# Schematic.net
KiCad netlist of a schematic drawn in EAGLE
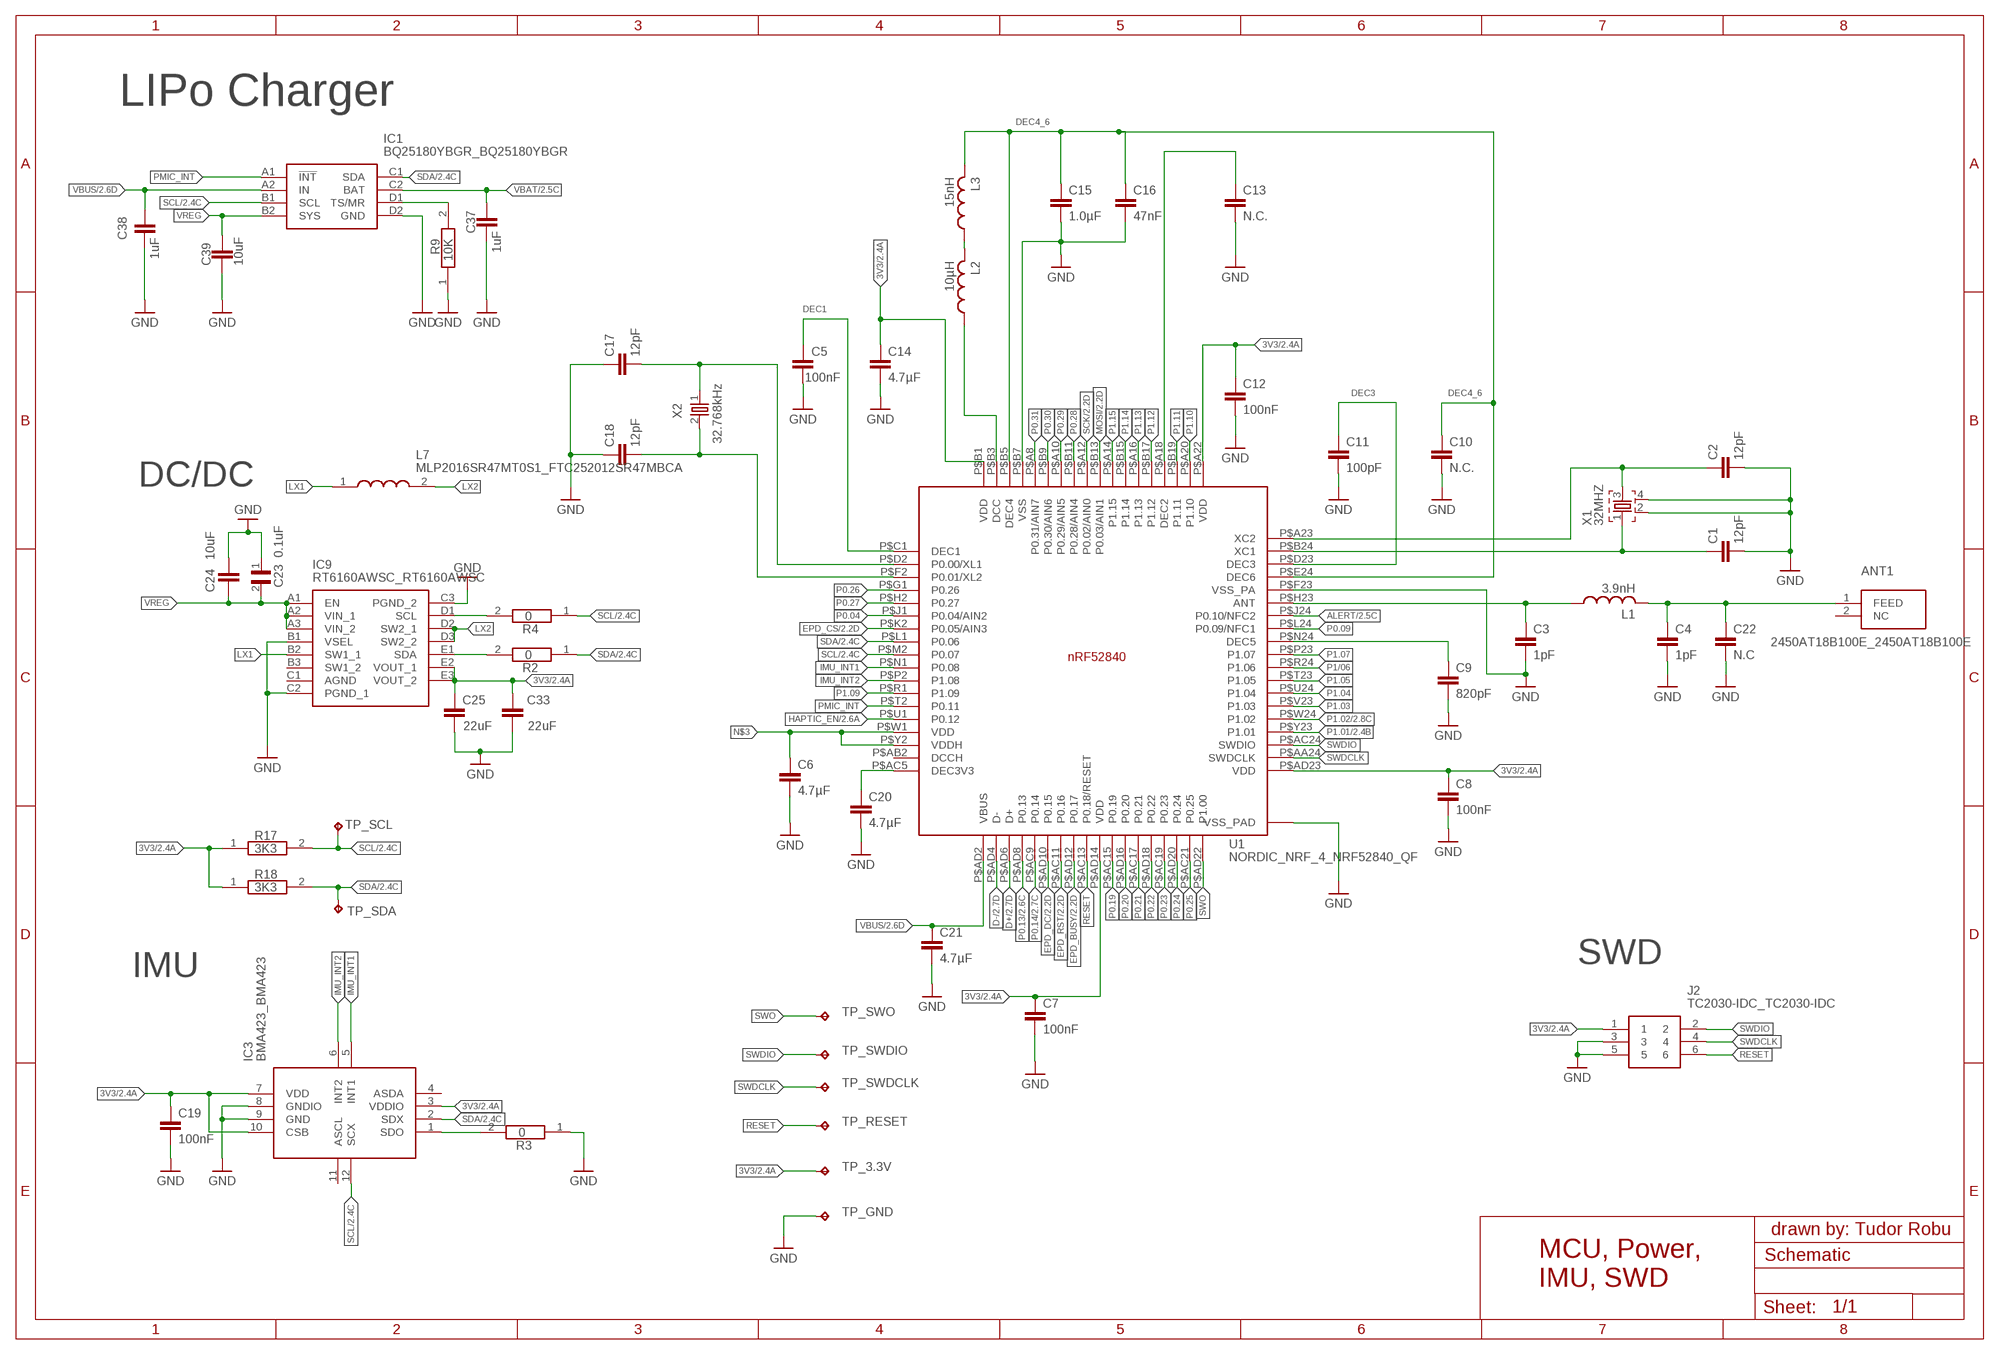
[diagram p0: schematic, sheet 1, part 1 of 2]
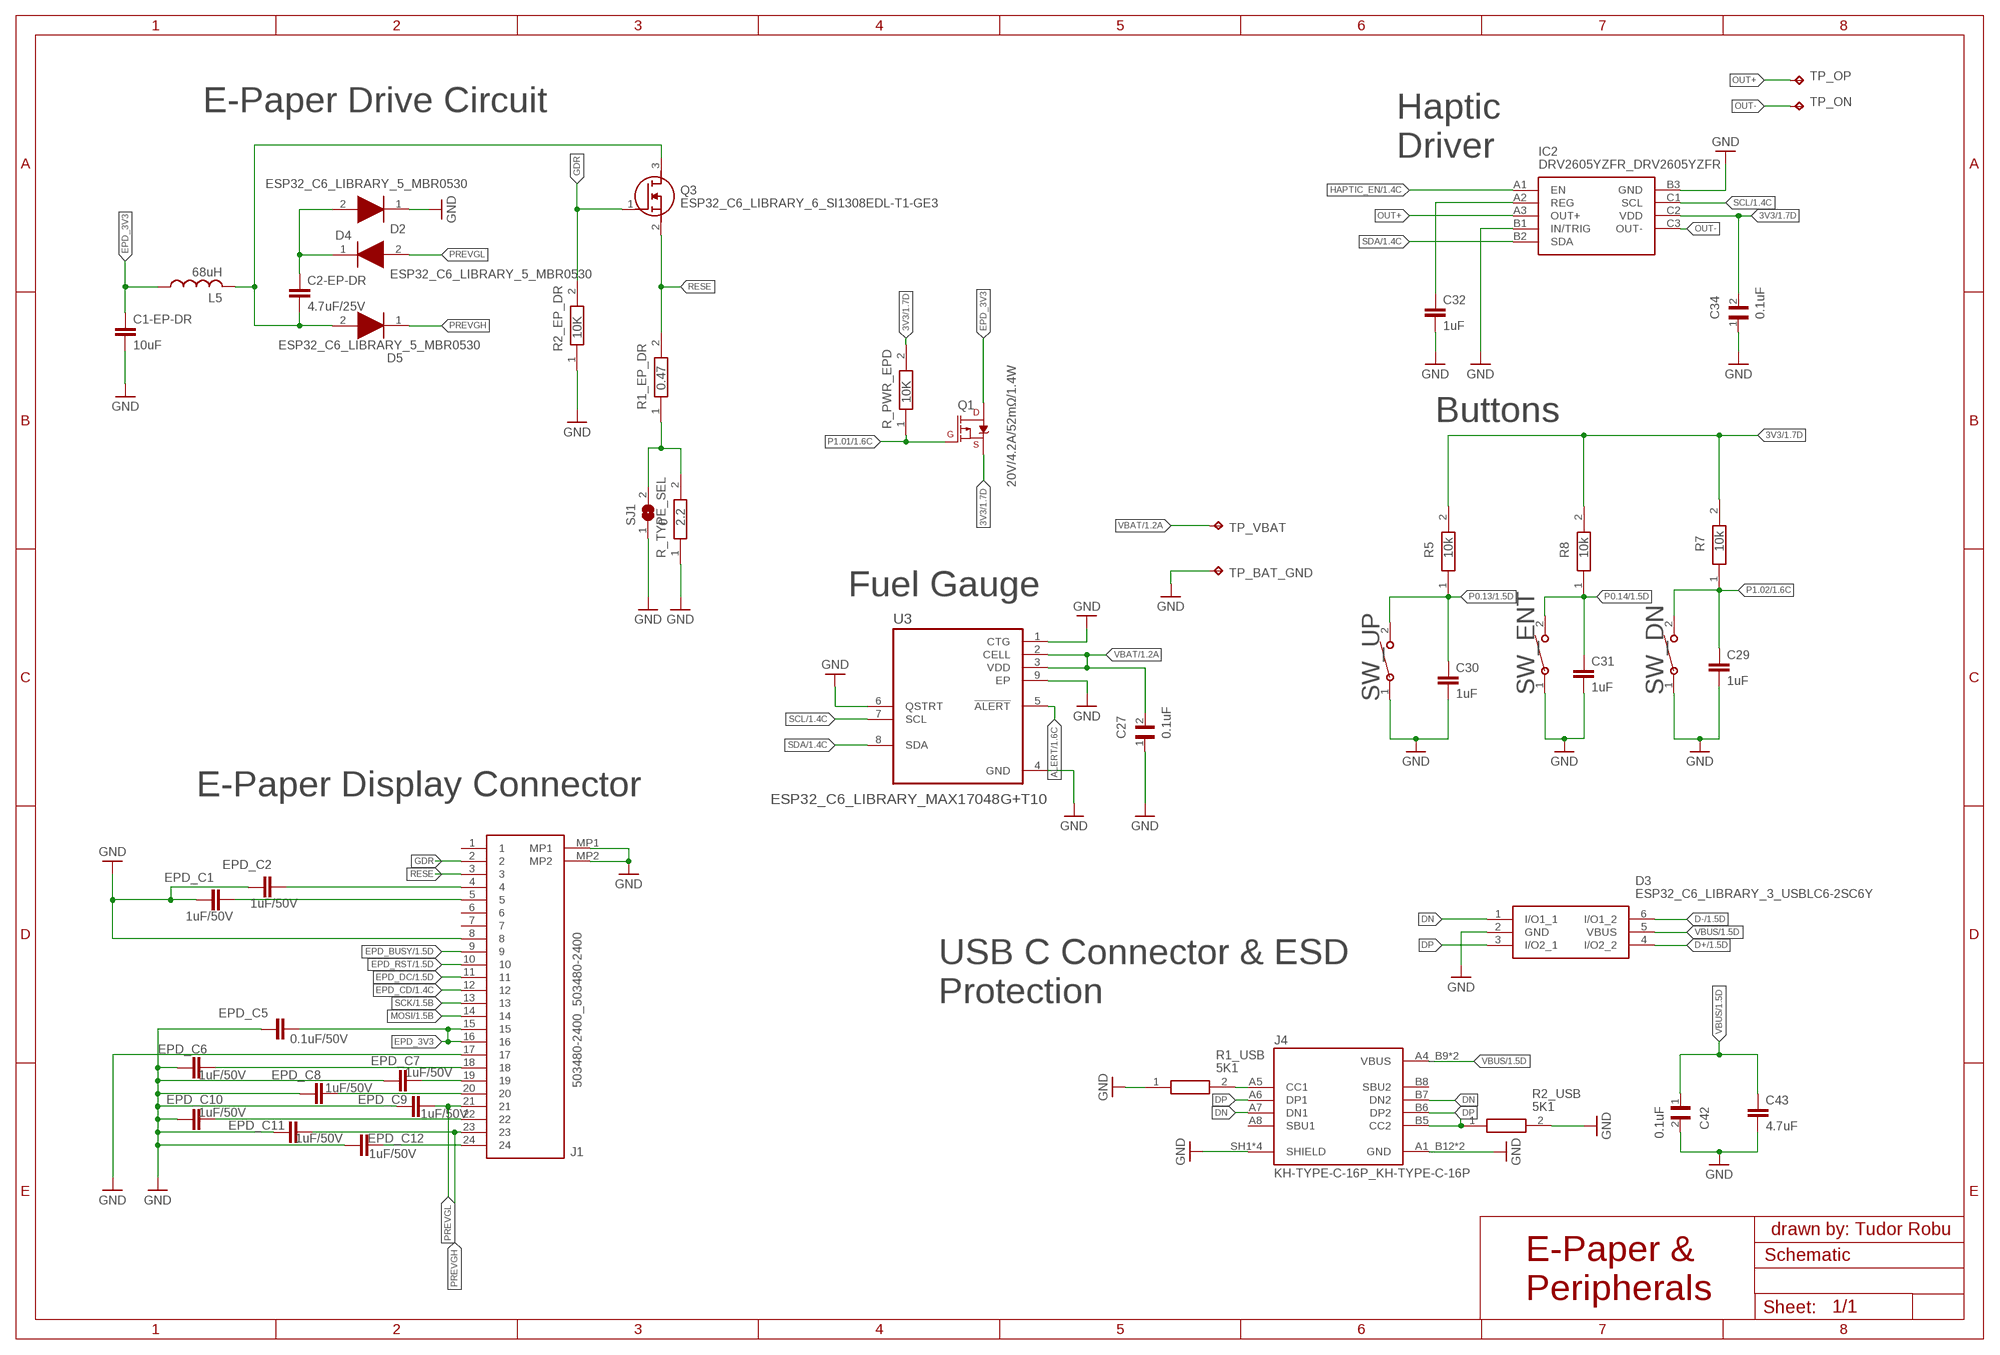
[diagram p1: schematic, sheet 1, part 2 of 2]

(export (version "E")
  (design (tool "Eeschema 10.0.6"))
  (components
    (comp (ref "ANT1")
      (value "2450AT18B100E_2450AT18B100E")
      (footprint "eagle-import:2450AT18B100E_ANTC3216X140N")
      (fields
        (field (name "ARROW_PART_NUMBER") "2450AT18B100E")
        (field (name "MOUSER_PART_NUMBER") "609-2450AT18B100E")
      )
      (libsource (lib "eagle-import") (part "2450AT18B100E_2450AT18B100E"))
    )
    (comp (ref "C1")
      (value "12pF")
      (footprint "eagle-import:NORDIC_NRF_3_RESC0201_L")
      (libsource (lib "eagle-import") (part "NORDIC_NRF_3_CAPACITOR_0201_L"))
    )
    (comp (ref "C1-EP-DR")
      (value "10uF")
      (footprint "eagle-import:PERFECT_0402_0402")
      (libsource (lib "eagle-import") (part "PERFECT_0402_CAP_0402"))
    )
    (comp (ref "C2")
      (value "12pF")
      (footprint "eagle-import:NORDIC_NRF_3_RESC0201_L")
      (libsource (lib "eagle-import") (part "NORDIC_NRF_3_CAPACITOR_0201_L"))
    )
    (comp (ref "C2-EP-DR")
      (value "4.7uF/25V")
      (footprint "eagle-import:PERFECT_0402_0402")
      (libsource (lib "eagle-import") (part "PERFECT_0402_CAP_0402"))
    )
    (comp (ref "C3")
      (value "1pF")
      (footprint "eagle-import:NORDIC_NRF_3_RESC0201_L")
      (libsource (lib "eagle-import") (part "NORDIC_NRF_3_CAPACITOR_0201_L"))
    )
    (comp (ref "C4")
      (value "1pF")
      (footprint "eagle-import:NORDIC_NRF_3_RESC0201_L")
      (libsource (lib "eagle-import") (part "NORDIC_NRF_3_CAPACITOR_0201_L"))
    )
    (comp (ref "C5")
      (value "100nF")
      (footprint "eagle-import:NORDIC_NRF_3_RESC0201_L")
      (libsource (lib "eagle-import") (part "NORDIC_NRF_3_CAPACITOR_0201_L"))
    )
    (comp (ref "C6")
      (value "4.7µF")
      (footprint "eagle-import:PERFECT_0402_0402")
      (libsource (lib "eagle-import") (part "PERFECT_0402_CAP_0402"))
    )
    (comp (ref "C7")
      (value "100nF")
      (footprint "eagle-import:PERFECT_0402_0402")
      (libsource (lib "eagle-import") (part "PERFECT_0402_CAP_0402"))
    )
    (comp (ref "C8")
      (value "100nF")
      (footprint "eagle-import:NORDIC_NRF_3_RESC0201_L")
      (libsource (lib "eagle-import") (part "NORDIC_NRF_3_CAPACITOR_0201_L"))
    )
    (comp (ref "C9")
      (value "820pF")
      (footprint "eagle-import:NORDIC_NRF_3_RESC0201_L")
      (libsource (lib "eagle-import") (part "NORDIC_NRF_3_CAPACITOR_0201_L"))
    )
    (comp (ref "C10")
      (value "N.C.")
      (footprint "eagle-import:NORDIC_NRF_3_RESC0201_L")
      (libsource (lib "eagle-import") (part "NORDIC_NRF_3_CAPACITOR_0201_L"))
    )
    (comp (ref "C11")
      (value "100pF")
      (footprint "eagle-import:NORDIC_NRF_3_RESC0201_L")
      (libsource (lib "eagle-import") (part "NORDIC_NRF_3_CAPACITOR_0201_L"))
    )
    (comp (ref "C12")
      (value "100nF")
      (footprint "eagle-import:NORDIC_NRF_3_RESC0201_L")
      (libsource (lib "eagle-import") (part "NORDIC_NRF_3_CAPACITOR_0201_L"))
    )
    (comp (ref "C13")
      (value "N.C.")
      (footprint "eagle-import:PERFECT_0402_0402")
      (libsource (lib "eagle-import") (part "PERFECT_0402_CAP_0402"))
    )
    (comp (ref "C14")
      (value "4.7µF")
      (footprint "eagle-import:PERFECT_0402_0402")
      (libsource (lib "eagle-import") (part "PERFECT_0402_CAP_0402"))
    )
    (comp (ref "C15")
      (value "1.0µF")
      (footprint "eagle-import:PERFECT_0402_0402")
      (libsource (lib "eagle-import") (part "PERFECT_0402_CAP_0402"))
    )
    (comp (ref "C16")
      (value "47nF")
      (footprint "eagle-import:NORDIC_NRF_3_RESC0201_L")
      (libsource (lib "eagle-import") (part "NORDIC_NRF_3_CAPACITOR_0201_L"))
    )
    (comp (ref "C17")
      (value "12pF")
      (footprint "eagle-import:NORDIC_NRF_3_RESC0201_L")
      (libsource (lib "eagle-import") (part "NORDIC_NRF_3_CAPACITOR_0201_L"))
    )
    (comp (ref "C18")
      (value "12pF")
      (footprint "eagle-import:NORDIC_NRF_3_RESC0201_L")
      (libsource (lib "eagle-import") (part "NORDIC_NRF_3_CAPACITOR_0201_L"))
    )
    (comp (ref "C19")
      (value "100nF")
      (footprint "eagle-import:NORDIC_NRF_3_RESC0201_L")
      (libsource (lib "eagle-import") (part "NORDIC_NRF_3_CAPACITOR_0201_L"))
    )
    (comp (ref "C20")
      (value "4.7µF")
      (footprint "eagle-import:PERFECT_0402_0402")
      (libsource (lib "eagle-import") (part "PERFECT_0402_CAP_0402"))
    )
    (comp (ref "C21")
      (value "4.7µF")
      (footprint "eagle-import:PERFECT_0402_0402")
      (libsource (lib "eagle-import") (part "PERFECT_0402_CAP_0402"))
    )
    (comp (ref "C22")
      (value "N.C")
      (footprint "eagle-import:NORDIC_NRF_3_RESC0201_L")
      (libsource (lib "eagle-import") (part "NORDIC_NRF_3_CAPACITOR_0201_L"))
    )
    (comp (ref "C23")
      (value "0.1uF")
      (footprint "eagle-import:GRM011R60J152KE01L_2_CAPC0201X13N")
      (fields (field (name "MF") "Murata") (field (name "MP") "GRM011R60J152KE01L"))
      (libsource (lib "eagle-import") (part "GRM011R60J152KE01L_2_GRM011R60J152KE01L"))
    )
    (comp (ref "C24")
      (value "10uF")
      (footprint "eagle-import:PERFECT_0402_0402")
      (libsource (lib "eagle-import") (part "PERFECT_0402_CAP_0402"))
    )
    (comp (ref "C25")
      (value "22uF")
      (footprint "eagle-import:PERFECT_0402_0402")
      (libsource (lib "eagle-import") (part "PERFECT_0402_CAP_0402"))
    )
    (comp (ref "C27")
      (value "0.1uF")
      (footprint "eagle-import:GRM011R60J152KE01L_2_CAPC0201X13N")
      (fields (field (name "MF") "Murata") (field (name "MP") "GRM011R60J152KE01L"))
      (libsource (lib "eagle-import") (part "GRM011R60J152KE01L_2_GRM011R60J152KE01L"))
    )
    (comp (ref "C29")
      (value "1uF")
      (footprint "eagle-import:PERFECT_0402_0402")
      (libsource (lib "eagle-import") (part "PERFECT_0402_CAP_0402"))
    )
    (comp (ref "C30")
      (value "1uF")
      (footprint "eagle-import:PERFECT_0402_0402")
      (libsource (lib "eagle-import") (part "PERFECT_0402_CAP_0402"))
    )
    (comp (ref "C31")
      (value "1uF")
      (footprint "eagle-import:PERFECT_0402_0402")
      (libsource (lib "eagle-import") (part "PERFECT_0402_CAP_0402"))
    )
    (comp (ref "C32")
      (value "1uF")
      (footprint "eagle-import:PERFECT_0402_0402")
      (libsource (lib "eagle-import") (part "PERFECT_0402_CAP_0402"))
    )
    (comp (ref "C33")
      (value "22uF")
      (footprint "eagle-import:PERFECT_0402_0402")
      (libsource (lib "eagle-import") (part "PERFECT_0402_CAP_0402"))
    )
    (comp (ref "C34")
      (value "0.1uF")
      (footprint "eagle-import:GRM011R60J152KE01L_2_CAPC0201X13N")
      (fields (field (name "MF") "Murata") (field (name "MP") "GRM011R60J152KE01L"))
      (libsource (lib "eagle-import") (part "GRM011R60J152KE01L_2_GRM011R60J152KE01L"))
    )
    (comp (ref "C37")
      (value "1uF")
      (footprint "eagle-import:PERFECT_0402_0402")
      (libsource (lib "eagle-import") (part "PERFECT_0402_CAP_0402"))
    )
    (comp (ref "C38")
      (value "1uF")
      (footprint "eagle-import:PERFECT_0402_0402")
      (libsource (lib "eagle-import") (part "PERFECT_0402_CAP_0402"))
    )
    (comp (ref "C39")
      (value "10uF")
      (footprint "eagle-import:PERFECT_0402_0402")
      (libsource (lib "eagle-import") (part "PERFECT_0402_CAP_0402"))
    )
    (comp (ref "C42")
      (value "0.1uF")
      (footprint "eagle-import:GRM011R60J152KE01L_2_CAPC0201X13N")
      (fields (field (name "MF") "Murata") (field (name "MP") "GRM011R60J152KE01L"))
      (libsource (lib "eagle-import") (part "GRM011R60J152KE01L_2_GRM011R60J152KE01L"))
    )
    (comp (ref "C43")
      (value "4.7uF")
      (footprint "eagle-import:PERFECT_0402_0402")
      (libsource (lib "eagle-import") (part "PERFECT_0402_CAP_0402"))
    )
    (comp (ref "D2")
      (value "ESP32_C6_LIBRARY_5_MBR0530")
      (footprint "eagle-import:ESP32_C6_LIBRARY_5_SOD3716X135N")
      (fields (field (name "MF") "ON Semiconductor") (field (name "MP") "MBR0530"))
      (libsource (lib "eagle-import") (part "ESP32_C6_LIBRARY_5_MBR0530"))
    )
    (comp (ref "D3")
      (value "ESP32_C6_LIBRARY_3_USBLC6-2SC6Y")
      (footprint "eagle-import:ESP32_C6_LIBRARY_3_SOT95P280X145-6N")
      (fields (field (name "MF") "STMicroelectronics") (field (name "MP") "USBLC6-2SC6Y"))
      (libsource (lib "eagle-import") (part "ESP32_C6_LIBRARY_3_USBLC6-2SC6Y"))
    )
    (comp (ref "D4")
      (value "ESP32_C6_LIBRARY_5_MBR0530")
      (footprint "eagle-import:ESP32_C6_LIBRARY_5_SOD3716X135N")
      (fields (field (name "MF") "ON Semiconductor") (field (name "MP") "MBR0530"))
      (libsource (lib "eagle-import") (part "ESP32_C6_LIBRARY_5_MBR0530"))
    )
    (comp (ref "D5")
      (value "ESP32_C6_LIBRARY_5_MBR0530")
      (footprint "eagle-import:ESP32_C6_LIBRARY_5_SOD3716X135N")
      (fields (field (name "MF") "ON Semiconductor") (field (name "MP") "MBR0530"))
      (libsource (lib "eagle-import") (part "ESP32_C6_LIBRARY_5_MBR0530"))
    )
    (comp (ref "EPD_C1")
      (value "1uF/50V")
      (footprint "eagle-import:PERFECT_0402_0402")
      (libsource (lib "eagle-import") (part "PERFECT_0402_CAP_0402"))
    )
    (comp (ref "EPD_C2")
      (value "1uF/50V")
      (footprint "eagle-import:PERFECT_0402_0402")
      (libsource (lib "eagle-import") (part "PERFECT_0402_CAP_0402"))
    )
    (comp (ref "EPD_C5")
      (value "0.1uF/50V")
      (footprint "eagle-import:NORDIC_NRF_3_RESC0201_L")
      (libsource (lib "eagle-import") (part "NORDIC_NRF_3_CAPACITOR_0201_L"))
    )
    (comp (ref "EPD_C6")
      (value "1uF/50V")
      (footprint "eagle-import:PERFECT_0402_0402")
      (libsource (lib "eagle-import") (part "PERFECT_0402_CAP_0402"))
    )
    (comp (ref "EPD_C7")
      (value "1uF/50V")
      (footprint "eagle-import:PERFECT_0402_0402")
      (libsource (lib "eagle-import") (part "PERFECT_0402_CAP_0402"))
    )
    (comp (ref "EPD_C8")
      (value "1uF/50V")
      (footprint "eagle-import:PERFECT_0402_0402")
      (libsource (lib "eagle-import") (part "PERFECT_0402_CAP_0402"))
    )
    (comp (ref "EPD_C9")
      (value "1uF/50V")
      (footprint "eagle-import:PERFECT_0402_0402")
      (libsource (lib "eagle-import") (part "PERFECT_0402_CAP_0402"))
    )
    (comp (ref "EPD_C10")
      (value "1uF/50V")
      (footprint "eagle-import:PERFECT_0402_0402")
      (libsource (lib "eagle-import") (part "PERFECT_0402_CAP_0402"))
    )
    (comp (ref "EPD_C11")
      (value "1uF/50V")
      (footprint "eagle-import:PERFECT_0402_0402")
      (libsource (lib "eagle-import") (part "PERFECT_0402_CAP_0402"))
    )
    (comp (ref "EPD_C12")
      (value "1uF/50V")
      (footprint "eagle-import:PERFECT_0402_0402")
      (libsource (lib "eagle-import") (part "PERFECT_0402_CAP_0402"))
    )
    (comp (ref "IC1")
      (value "BQ25180YBGR_BQ25180YBGR")
      (footprint "eagle-import:BQ25180YBGR_BGA8C40P2X4_100X155X50")
      (fields
        (field (name "ARROW_PART_NUMBER") "BQ25180YBGR")
        (field (name "MOUSER_PART_NUMBER") "595-BQ25180YBGR")
      )
      (libsource (lib "eagle-import") (part "BQ25180YBGR_BQ25180YBGR"))
    )
    (comp (ref "IC2")
      (value "DRV2605YZFR_DRV2605YZFR")
      (footprint "eagle-import:DRV2605YZFR_BGA9C50P3X3_144X144X62")
      (fields (field (name "ARROW_PART_NUMBER") "DRV2605YZFR"))
      (libsource (lib "eagle-import") (part "DRV2605YZFR_DRV2605YZFR"))
    )
    (comp (ref "IC3")
      (value "BMA423_BMA423")
      (footprint "eagle-import:BMA423_BMA423")
      (fields (field (name "ARROW_PART_NUMBER") "BMA423") (field (name "MOUSER_PART_NUMBER") "262-BMA423"))
      (libsource (lib "eagle-import") (part "BMA423_BMA423"))
    )
    (comp (ref "IC9")
      (value "RT6160AWSC_RT6160AWSC")
      (footprint "eagle-import:RT6160AWSC_BGA15C40P3X5_140X230X60")
      (fields
        (field (name "MANUFACTURER_PART_NUMBER") "RT6160AWSC")
        (field (name "MOUSER_PART_NUMBER") "835-RT6160AWSC")
      )
      (libsource (lib "eagle-import") (part "RT6160AWSC_RT6160AWSC"))
    )
    (comp (ref "J1")
      (value "503480-2400_503480-2400")
      (footprint "eagle-import:503480-2400_5034802400")
      (fields
        (field (name "MANUFACTURER_PART_NUMBER") "503480-2400")
        (field (name "MOUSER_PART_NUMBER") "538-503480-2400")
      )
      (libsource (lib "eagle-import") (part "503480-2400_503480-2400"))
    )
    (comp (ref "J2")
      (value "TC2030-IDC_TC2030-IDC")
      (footprint "eagle-import:TC2030-IDC_TC2030IDC")
      (fields (field (name "MANUFACTURER_PART_NUMBER") "TC2030-IDC"))
      (libsource (lib "eagle-import") (part "TC2030-IDC_TC2030-IDC"))
    )
    (comp (ref "J4")
      (value "KH-TYPE-C-16P_KH-TYPE-C-16P")
      (footprint "eagle-import:KH-TYPE-C-16P_KINGHELM_KH-TYPE-C-16P")
      (fields (field (name "MF") "kinghelm") (field (name "MP") "KH-TYPE-C-16P"))
      (libsource (lib "eagle-import") (part "KH-TYPE-C-16P_KH-TYPE-C-16P"))
    )
    (comp (ref "L1")
      (value "3.9nH")
      (footprint "eagle-import:NORDIC_NRF_2_RESC0402_L")
      (libsource (lib "eagle-import") (part "NORDIC_NRF_2_INDUCTOR_0402_L"))
    )
    (comp (ref "L2")
      (value "10µH")
      (footprint "eagle-import:NORDIC_NRF_2_RESC0402_L")
      (libsource (lib "eagle-import") (part "NORDIC_NRF_2_INDUCTOR_0402_L"))
    )
    (comp (ref "L3")
      (value "15nH")
      (footprint "eagle-import:NORDIC_NRF_2_RESC0402_L")
      (libsource (lib "eagle-import") (part "NORDIC_NRF_2_INDUCTOR_0402_L"))
    )
    (comp (ref "L5")
      (value "68uH")
      (footprint "eagle-import:NORDIC_NRF_2_RESC0402_L")
      (libsource (lib "eagle-import") (part "NORDIC_NRF_2_INDUCTOR_0402_L"))
    )
    (comp (ref "L7")
      (value "MLP2016SR47MT0S1_FTC252012SR47MBCA")
      (footprint "eagle-import:MLP2016SR47MT0S1_INDC2016X100N")
      (fields (field (name "MANUFACTURER_PART_NUMBER") "FTC252012SR47MBCA"))
      (libsource (lib "eagle-import") (part "MLP2016SR47MT0S1_FTC252012SR47MBCA"))
    )
    (comp (ref "Q1")
      (value "20V/4.2A/52mΩ/1.4W")
      (footprint "eagle-import:ESP32_C6_LIBRARY_4_ESP32_C6_LIBRARY_4_ESP32_C6_LIBRARY_4_ESP32_C6_LIBRARY_4_ESP32_WROVER_SPARKFUN-DISCRETESEMI_SOT23-3")
      (libsource (lib "eagle-import") (part "ESP32_C6_LIBRARY_4_ESP32_WROVER_SPARKFUN-DISCRETESEMI_MOSFET_PCH-DMG2305UX-7"))
    )
    (comp (ref "Q3")
      (value "ESP32_C6_LIBRARY_6_SI1308EDL-T1-GE3")
      (footprint "eagle-import:ESP32_C6_LIBRARY_6_SOT65P210X110-3N")
      (fields (field (name "MF") "Vishay Siliconix") (field (name "MP") "SI1308EDL-T1-GE3"))
      (libsource (lib "eagle-import") (part "ESP32_C6_LIBRARY_6_SI1308EDL-T1-GE3"))
    )
    (comp (ref "R1_EP_DR")
      (value "0.47")
      (footprint "eagle-import:CPF0201D7K68C1_0201")
      (libsource (lib "eagle-import") (part "CPF0201D7K68C1_CPF0201D7K68C1"))
    )
    (comp (ref "R1_USB")
      (value "5K1")
      (footprint "eagle-import:CPF0201D7K68C1_0201")
      (libsource (lib "eagle-import") (part "CPF0201D7K68C1_CPF0201D7K68C1"))
    )
    (comp (ref "R2")
      (value "0")
      (footprint "eagle-import:ERA-1AEB3401C_0201")
      (libsource (lib "eagle-import") (part "ERA-1AEB3401C_CPF0201D7K68C1"))
    )
    (comp (ref "R2_EP_DR")
      (value "10K")
      (footprint "eagle-import:CPF0201D7K68C1_0201")
      (libsource (lib "eagle-import") (part "CPF0201D7K68C1_CPF0201D7K68C1"))
    )
    (comp (ref "R2_USB")
      (value "5K1")
      (footprint "eagle-import:CPF0201D7K68C1_0201")
      (libsource (lib "eagle-import") (part "CPF0201D7K68C1_CPF0201D7K68C1"))
    )
    (comp (ref "R3")
      (value "0")
      (footprint "eagle-import:ERA-1AEB3401C_0201")
      (libsource (lib "eagle-import") (part "ERA-1AEB3401C_CPF0201D7K68C1"))
    )
    (comp (ref "R4")
      (value "0")
      (footprint "eagle-import:ERA-1AEB3401C_0201")
      (libsource (lib "eagle-import") (part "ERA-1AEB3401C_CPF0201D7K68C1"))
    )
    (comp (ref "R5")
      (value "10k")
      (footprint "eagle-import:CPF0201D7K68C1_0201")
      (libsource (lib "eagle-import") (part "CPF0201D7K68C1_CPF0201D7K68C1"))
    )
    (comp (ref "R7")
      (value "10k")
      (footprint "eagle-import:CPF0201D7K68C1_0201")
      (libsource (lib "eagle-import") (part "CPF0201D7K68C1_CPF0201D7K68C1"))
    )
    (comp (ref "R8")
      (value "10k")
      (footprint "eagle-import:CPF0201D7K68C1_0201")
      (libsource (lib "eagle-import") (part "CPF0201D7K68C1_CPF0201D7K68C1"))
    )
    (comp (ref "R9")
      (value "10K")
      (footprint "eagle-import:CPF0201D7K68C1_0201")
      (libsource (lib "eagle-import") (part "CPF0201D7K68C1_CPF0201D7K68C1"))
    )
    (comp (ref "R17")
      (value "3K3")
      (footprint "eagle-import:ERA-1AEB3401C_0201")
      (libsource (lib "eagle-import") (part "ERA-1AEB3401C_CPF0201D7K68C1"))
    )
    (comp (ref "R18")
      (value "3K3")
      (footprint "eagle-import:ERA-1AEB3401C_0201")
      (libsource (lib "eagle-import") (part "ERA-1AEB3401C_CPF0201D7K68C1"))
    )
    (comp (ref "R_PWR_EPD")
      (value "10K")
      (footprint "eagle-import:CPF0201D7K68C1_0201")
      (libsource (lib "eagle-import") (part "CPF0201D7K68C1_CPF0201D7K68C1"))
    )
    (comp (ref "R_TYPE_SEL")
      (value "2.2")
      (footprint "eagle-import:CPF0201D7K68C1_0201")
      (libsource (lib "eagle-import") (part "CPF0201D7K68C1_CPF0201D7K68C1"))
    )
    (comp (ref "SJ1")
      (value "0")
      (footprint "eagle-import:ESP32_C6_LIBRARY_7_JUMPER_SJ")
      (libsource (lib "eagle-import") (part "ESP32_C6_LIBRARY_7_JUMPER_SJ"))
    )
    (comp (ref "SW_DN")
      (value "2025-10-22_07-23-44_LIBRARY_EVP-AKE31ASW_EVP-AKE31A_PAN")
      (footprint "eagle-import:2025-10-22_07-23-44_LIBRARY_SW_EVP-AKE31A_PAN")
      (fields
        (field (name "MANUFACTURER_PART_NUMBER") "EVP-AKE31A")
        (field (name "COPYRIGHT") "Copyright (C) 2025 Ultra Librarian. All rights reserved.")
      )
      (libsource (lib "eagle-import") (part "2025-10-22_07-23-44_LIBRARY_EVP-AKE31ASW_EVP-AKE31A_PAN"))
    )
    (comp (ref "SW_ENT")
      (value "2025-10-22_07-23-44_LIBRARY_EVP-AKE31ASW_EVP-AKE31A_PAN")
      (footprint "eagle-import:2025-10-22_07-23-44_LIBRARY_SW_EVP-AKE31A_PAN")
      (fields
        (field (name "MANUFACTURER_PART_NUMBER") "EVP-AKE31A")
        (field (name "COPYRIGHT") "Copyright (C) 2025 Ultra Librarian. All rights reserved.")
      )
      (libsource (lib "eagle-import") (part "2025-10-22_07-23-44_LIBRARY_EVP-AKE31ASW_EVP-AKE31A_PAN"))
    )
    (comp (ref "SW_UP")
      (value "2025-10-22_07-23-44_LIBRARY_EVP-AKE31ASW_EVP-AKE31A_PAN")
      (footprint "eagle-import:2025-10-22_07-23-44_LIBRARY_SW_EVP-AKE31A_PAN")
      (fields
        (field (name "MANUFACTURER_PART_NUMBER") "EVP-AKE31A")
        (field (name "COPYRIGHT") "Copyright (C) 2025 Ultra Librarian. All rights reserved.")
      )
      (libsource (lib "eagle-import") (part "2025-10-22_07-23-44_LIBRARY_EVP-AKE31ASW_EVP-AKE31A_PAN"))
    )
    (comp (ref "TP_3.3V")
      (value "HECTOR_WATCH_1_TPTP20R")
      (footprint "eagle-import:HECTOR_WATCH_1_TP20R")
      (libsource (lib "eagle-import") (part "HECTOR_WATCH_1_TPTP20R"))
    )
    (comp (ref "TP_BAT_GND")
      (value "HECTOR_WATCH_1_TPTP20R")
      (footprint "eagle-import:HECTOR_WATCH_1_TP20R")
      (libsource (lib "eagle-import") (part "HECTOR_WATCH_1_TPTP20R"))
    )
    (comp (ref "TP_GND")
      (value "HECTOR_WATCH_1_TPTP20R")
      (footprint "eagle-import:HECTOR_WATCH_1_TP20R")
      (libsource (lib "eagle-import") (part "HECTOR_WATCH_1_TPTP20R"))
    )
    (comp (ref "TP_ON")
      (value "HECTOR_WATCH_1_TPTP20R")
      (footprint "eagle-import:HECTOR_WATCH_1_TP20R")
      (libsource (lib "eagle-import") (part "HECTOR_WATCH_1_TPTP20R"))
    )
    (comp (ref "TP_OP")
      (value "HECTOR_WATCH_1_TPTP20R")
      (footprint "eagle-import:HECTOR_WATCH_1_TP20R")
      (libsource (lib "eagle-import") (part "HECTOR_WATCH_1_TPTP20R"))
    )
    (comp (ref "TP_RESET")
      (value "HECTOR_WATCH_1_TPTP20R")
      (footprint "eagle-import:HECTOR_WATCH_1_TP20R")
      (libsource (lib "eagle-import") (part "HECTOR_WATCH_1_TPTP20R"))
    )
    (comp (ref "TP_SCL")
      (value "HECTOR_WATCH_1_TPTP20R")
      (footprint "eagle-import:HECTOR_WATCH_1_TP20R")
      (libsource (lib "eagle-import") (part "HECTOR_WATCH_1_TPTP20R"))
    )
    (comp (ref "TP_SDA")
      (value "HECTOR_WATCH_1_TPTP20R")
      (footprint "eagle-import:HECTOR_WATCH_1_TP20R")
      (libsource (lib "eagle-import") (part "HECTOR_WATCH_1_TPTP20R"))
    )
    (comp (ref "TP_SWDCLK")
      (value "HECTOR_WATCH_1_TPTP20R")
      (footprint "eagle-import:HECTOR_WATCH_1_TP20R")
      (libsource (lib "eagle-import") (part "HECTOR_WATCH_1_TPTP20R"))
    )
    (comp (ref "TP_SWDIO")
      (value "HECTOR_WATCH_1_TPTP20R")
      (footprint "eagle-import:HECTOR_WATCH_1_TP20R")
      (libsource (lib "eagle-import") (part "HECTOR_WATCH_1_TPTP20R"))
    )
    (comp (ref "TP_SWO")
      (value "HECTOR_WATCH_1_TPTP20R")
      (footprint "eagle-import:HECTOR_WATCH_1_TP20R")
      (libsource (lib "eagle-import") (part "HECTOR_WATCH_1_TPTP20R"))
    )
    (comp (ref "TP_VBAT")
      (value "HECTOR_WATCH_1_TPTP20R")
      (footprint "eagle-import:HECTOR_WATCH_1_TP20R")
      (libsource (lib "eagle-import") (part "HECTOR_WATCH_1_TPTP20R"))
    )
    (comp (ref "U1")
      (value "NORDIC_NRF_4_NRF52840_QF")
      (footprint "eagle-import:NORDIC_NRF_4_AQFN50P700X700X85_HS-74N")
      (libsource (lib "eagle-import") (part "NORDIC_NRF_4_NRF52840_QF"))
    )
    (comp (ref "U3")
      (value "ESP32_C6_LIBRARY_MAX17048G+T10")
      (footprint "eagle-import:ESP32_C6_LIBRARY_SON50P200X200X80-9N")
      (fields (field (name "MF") "Analog Devices") (field (name "MP") "MAX17048G+T10"))
      (libsource (lib "eagle-import") (part "ESP32_C6_LIBRARY_MAX17048G+T10"))
    )
    (comp (ref "X1")
      (value "32MHZ")
      (footprint "eagle-import:NORDIC_NRF_BT-XTAL_2016_N")
      (libsource (lib "eagle-import") (part "NORDIC_NRF_XTAL_32MHZ"))
    )
    (comp (ref "X2")
      (value "32.768kHz")
      (footprint "eagle-import:NORDIC_NRF_1_XTAL_3215_N")
      (libsource (lib "eagle-import") (part "NORDIC_NRF_1_XTAL_32KHZ"))
    )
  )
  (nets
    (net (code "1") (name "3V3{slash}1.7D") (class "Default")
      (node (ref "C34") (pin "2") (pinfunction "2_2") (pintype "passive"))
      (node (ref "IC2") (pin "C2") (pinfunction "VDD_C2") (pintype "bidirectional"))
      (node (ref "Q1") (pin "2") (pinfunction "S_2") (pintype "bidirectional"))
      (node (ref "R5") (pin "2") (pinfunction "2_2") (pintype "bidirectional"))
      (node (ref "R7") (pin "2") (pinfunction "2_2") (pintype "bidirectional"))
      (node (ref "R8") (pin "2") (pinfunction "2_2") (pintype "bidirectional"))
      (node (ref "R_PWR_EPD") (pin "2") (pinfunction "2_2") (pintype "bidirectional"))
    )
    (net (code "2") (name "3V3{slash}2.4A") (class "Default")
      (node (ref "C12") (pin "1") (pinfunction "1_1") (pintype "passive"))
      (node (ref "C14") (pin "1") (pinfunction "1_1") (pintype "passive"))
      (node (ref "C19") (pin "1") (pinfunction "1_1") (pintype "passive"))
      (node (ref "C25") (pin "2") (pinfunction "2_2") (pintype "passive"))
      (node (ref "C33") (pin "2") (pinfunction "2_2") (pintype "passive"))
      (node (ref "C7") (pin "1") (pinfunction "1_1") (pintype "passive"))
      (node (ref "C8") (pin "1") (pinfunction "1_1") (pintype "passive"))
      (node (ref "IC3") (pin "10") (pinfunction "CSB_10") (pintype "bidirectional"))
      (node (ref "IC3") (pin "3") (pinfunction "VDDIO_3") (pintype "bidirectional"))
      (node (ref "IC3") (pin "7") (pinfunction "VDD_7") (pintype "bidirectional"))
      (node (ref "IC9") (pin "E2") (pinfunction "VOUT_1_E2") (pintype "bidirectional"))
      (node (ref "IC9") (pin "E3") (pinfunction "VOUT_2_E3") (pintype "bidirectional"))
      (node (ref "J2") (pin "1") (pinfunction "1_1") (pintype "bidirectional"))
      (node (ref "R17") (pin "1") (pinfunction "1_1") (pintype "bidirectional"))
      (node (ref "R18") (pin "1") (pinfunction "1_1") (pintype "bidirectional"))
      (node (ref "TP_3.3V") (pin "TP") (pinfunction "TP_TP") (pintype "input"))
      (node (ref "U1") (pin "P$A22") (pinfunction "VDD_P$A22") (pintype "power_in"))
      (node (ref "U1") (pin "P$AD14") (pinfunction "VDD_P$AD14") (pintype "power_in"))
      (node (ref "U1") (pin "P$AD23") (pinfunction "VDD_P$AD23") (pintype "power_in"))
      (node (ref "U1") (pin "P$B1") (pinfunction "VDD_P$B1") (pintype "power_in"))
    )
    (net (code "3") (name "ALERT{slash}1.6C") (class "Default")
      (node (ref "U3") (pin "5") (pinfunction "~{ALERT}_5") (pintype "output"))
    )
    (net (code "4") (name "ALERT{slash}2.5C") (class "Default")
      (node (ref "U1") (pin "P$J24") (pinfunction "P0.10/NFC2_P$J24") (pintype "bidirectional"))
    )
    (net (code "5") (name "D+{slash}1.5D") (class "Default")
      (node (ref "D3") (pin "4") (pinfunction "I/O2_2_4") (pintype "bidirectional"))
    )
    (net (code "6") (name "D+{slash}2.7D") (class "Default")
      (node (ref "U1") (pin "P$AD6") (pinfunction "D+_P$AD6") (pintype "bidirectional"))
    )
    (net (code "7") (name "D-{slash}1.5D") (class "Default")
      (node (ref "D3") (pin "6") (pinfunction "I/O1_2_6") (pintype "bidirectional"))
    )
    (net (code "8") (name "D-{slash}2.7D") (class "Default")
      (node (ref "U1") (pin "P$AD4") (pinfunction "D-_P$AD4") (pintype "bidirectional"))
    )
    (net (code "9") (name "DN") (class "Default")
      (node (ref "D3") (pin "1") (pinfunction "I/O1_1_1") (pintype "bidirectional"))
      (node (ref "J4") (pin "A7") (pinfunction "DN1_A7") (pintype "bidirectional"))
      (node (ref "J4") (pin "B7") (pinfunction "DN2_B7") (pintype "bidirectional"))
    )
    (net (code "10") (name "DP") (class "Default")
      (node (ref "D3") (pin "3") (pinfunction "I/O2_1_3") (pintype "bidirectional"))
      (node (ref "J4") (pin "A6") (pinfunction "DP1_A6") (pintype "bidirectional"))
      (node (ref "J4") (pin "B6") (pinfunction "DP2_B6") (pintype "bidirectional"))
    )
    (net (code "11") (name "EPD_3V3") (class "Default")
      (node (ref "C1-EP-DR") (pin "1") (pinfunction "1_1") (pintype "passive"))
      (node (ref "EPD_C5") (pin "2") (pinfunction "2_2") (pintype "passive"))
      (node (ref "J1") (pin "15") (pinfunction "15_15") (pintype "bidirectional"))
      (node (ref "J1") (pin "16") (pinfunction "16_16") (pintype "bidirectional"))
      (node (ref "L5") (pin "1") (pinfunction "1_1") (pintype "passive"))
      (node (ref "Q1") (pin "3") (pinfunction "D_3") (pintype "bidirectional"))
    )
    (net (code "12") (name "EPD_BUSY{slash}1.5D") (class "Default")
      (node (ref "J1") (pin "9") (pinfunction "9_9") (pintype "bidirectional"))
    )
    (net (code "13") (name "EPD_BUSY{slash}2.2D") (class "Default")
      (node (ref "U1") (pin "P$AC11") (pinfunction "P0.16_P$AC11") (pintype "bidirectional"))
    )
    (net (code "14") (name "EPD_CD{slash}1.4C") (class "Default")
      (node (ref "J1") (pin "12") (pinfunction "12_12") (pintype "bidirectional"))
    )
    (net (code "15") (name "EPD_CS{slash}2.2D") (class "Default")
      (node (ref "U1") (pin "P$K2") (pinfunction "P0.05/AIN3_P$K2") (pintype "bidirectional"))
    )
    (net (code "16") (name "EPD_DC{slash}1.5D") (class "Default")
      (node (ref "J1") (pin "11") (pinfunction "11_11") (pintype "bidirectional"))
    )
    (net (code "17") (name "EPD_DC{slash}2.2D") (class "Default")
      (node (ref "U1") (pin "P$AD10") (pinfunction "P0.15_P$AD10") (pintype "bidirectional"))
    )
    (net (code "18") (name "EPD_RST{slash}1.5D") (class "Default")
      (node (ref "J1") (pin "10") (pinfunction "10_10") (pintype "bidirectional"))
    )
    (net (code "19") (name "EPD_RST{slash}2.2D") (class "Default")
      (node (ref "U1") (pin "P$AD12") (pinfunction "P0.17_P$AD12") (pintype "bidirectional"))
    )
    (net (code "20") (name "GDR") (class "Default")
      (node (ref "J1") (pin "2") (pinfunction "2_2") (pintype "bidirectional"))
      (node (ref "Q3") (pin "1") (pinfunction "G_1") (pintype "bidirectional"))
      (node (ref "R2_EP_DR") (pin "2") (pinfunction "2_2") (pintype "bidirectional"))
    )
    (net (code "21") (name "GND") (class "Default")
      (node (ref "C1") (pin "2") (pinfunction "2_2") (pintype "passive"))
      (node (ref "C1-EP-DR") (pin "2") (pinfunction "2_2") (pintype "passive"))
      (node (ref "C10") (pin "2") (pinfunction "2_2") (pintype "passive"))
      (node (ref "C11") (pin "2") (pinfunction "2_2") (pintype "passive"))
      (node (ref "C12") (pin "2") (pinfunction "2_2") (pintype "passive"))
      (node (ref "C13") (pin "2") (pinfunction "2_2") (pintype "passive"))
      (node (ref "C14") (pin "2") (pinfunction "2_2") (pintype "passive"))
      (node (ref "C15") (pin "2") (pinfunction "2_2") (pintype "passive"))
      (node (ref "C16") (pin "2") (pinfunction "2_2") (pintype "passive"))
      (node (ref "C17") (pin "1") (pinfunction "1_1") (pintype "passive"))
      (node (ref "C18") (pin "1") (pinfunction "1_1") (pintype "passive"))
      (node (ref "C19") (pin "2") (pinfunction "2_2") (pintype "passive"))
      (node (ref "C2") (pin "2") (pinfunction "2_2") (pintype "passive"))
      (node (ref "C20") (pin "2") (pinfunction "2_2") (pintype "passive"))
      (node (ref "C21") (pin "2") (pinfunction "2_2") (pintype "passive"))
      (node (ref "C22") (pin "2") (pinfunction "2_2") (pintype "passive"))
      (node (ref "C23") (pin "1") (pinfunction "1_1") (pintype "passive"))
      (node (ref "C24") (pin "2") (pinfunction "2_2") (pintype "passive"))
      (node (ref "C25") (pin "1") (pinfunction "1_1") (pintype "passive"))
      (node (ref "C27") (pin "1") (pinfunction "1_1") (pintype "passive"))
      (node (ref "C29") (pin "2") (pinfunction "2_2") (pintype "passive"))
      (node (ref "C3") (pin "2") (pinfunction "2_2") (pintype "passive"))
      (node (ref "C30") (pin "2") (pinfunction "2_2") (pintype "passive"))
      (node (ref "C31") (pin "2") (pinfunction "2_2") (pintype "passive"))
      (node (ref "C32") (pin "2") (pinfunction "2_2") (pintype "passive"))
      (node (ref "C33") (pin "1") (pinfunction "1_1") (pintype "passive"))
      (node (ref "C34") (pin "1") (pinfunction "1_1") (pintype "passive"))
      (node (ref "C37") (pin "2") (pinfunction "2_2") (pintype "passive"))
      (node (ref "C38") (pin "2") (pinfunction "2_2") (pintype "passive"))
      (node (ref "C39") (pin "2") (pinfunction "2_2") (pintype "passive"))
      (node (ref "C4") (pin "2") (pinfunction "2_2") (pintype "passive"))
      (node (ref "C42") (pin "2") (pinfunction "2_2") (pintype "passive"))
      (node (ref "C43") (pin "2") (pinfunction "2_2") (pintype "passive"))
      (node (ref "C5") (pin "1") (pinfunction "1_1") (pintype "passive"))
      (node (ref "C6") (pin "2") (pinfunction "2_2") (pintype "passive"))
      (node (ref "C7") (pin "2") (pinfunction "2_2") (pintype "passive"))
      (node (ref "C8") (pin "2") (pinfunction "2_2") (pintype "passive"))
      (node (ref "C9") (pin "2") (pinfunction "2_2") (pintype "passive"))
      (node (ref "D3") (pin "2") (pinfunction "GND_2") (pintype "bidirectional"))
      (node (ref "D4") (pin "1") (pinfunction "K_1") (pintype "bidirectional"))
      (node (ref "EPD_C1") (pin "1") (pinfunction "1_1") (pintype "passive"))
      (node (ref "EPD_C10") (pin "1") (pinfunction "1_1") (pintype "passive"))
      (node (ref "EPD_C11") (pin "1") (pinfunction "1_1") (pintype "passive"))
      (node (ref "EPD_C12") (pin "1") (pinfunction "1_1") (pintype "passive"))
      (node (ref "EPD_C2") (pin "1") (pinfunction "1_1") (pintype "passive"))
      (node (ref "EPD_C5") (pin "1") (pinfunction "1_1") (pintype "passive"))
      (node (ref "EPD_C6") (pin "1") (pinfunction "1_1") (pintype "passive"))
      (node (ref "EPD_C7") (pin "1") (pinfunction "1_1") (pintype "passive"))
      (node (ref "EPD_C8") (pin "1") (pinfunction "1_1") (pintype "passive"))
      (node (ref "EPD_C9") (pin "1") (pinfunction "1_1") (pintype "passive"))
      (node (ref "IC1") (pin "D2") (pinfunction "GND_D2") (pintype "bidirectional"))
      (node (ref "IC2") (pin "B1") (pinfunction "IN/TRIG_B1") (pintype "bidirectional"))
      (node (ref "IC2") (pin "B3") (pinfunction "GND_B3") (pintype "bidirectional"))
      (node (ref "IC3") (pin "8") (pinfunction "GNDIO_8") (pintype "bidirectional"))
      (node (ref "IC3") (pin "9") (pinfunction "GND_9") (pintype "bidirectional"))
      (node (ref "IC9") (pin "B1") (pinfunction "VSEL_B1") (pintype "bidirectional"))
      (node (ref "IC9") (pin "C2") (pinfunction "PGND_1_C2") (pintype "bidirectional"))
      (node (ref "IC9") (pin "C3") (pinfunction "PGND_2_C3") (pintype "bidirectional"))
      (node (ref "J1") (pin "17") (pinfunction "17_17") (pintype "bidirectional"))
      (node (ref "J1") (pin "8") (pinfunction "8_8") (pintype "bidirectional"))
      (node (ref "J1") (pin "MP1") (pinfunction "MP1_MP1") (pintype "bidirectional"))
      (node (ref "J1") (pin "MP2") (pinfunction "MP2_MP2") (pintype "bidirectional"))
      (node (ref "J2") (pin "3") (pinfunction "3_3") (pintype "bidirectional"))
      (node (ref "J2") (pin "5") (pinfunction "5_5") (pintype "bidirectional"))
      (node (ref "J4") (pin "A12_B1") (pinfunction "GND_A12_B1") (pintype "power_in"))
      (node (ref "J4") (pin "A1_B12") (pinfunction "GND_A1_B12") (pintype "power_in"))
      (node (ref "J4") (pin "SH1") (pinfunction "SHIELD_SH1") (pintype "passive"))
      (node (ref "J4") (pin "SH2") (pinfunction "SHIELD_SH2") (pintype "passive"))
      (node (ref "J4") (pin "SH3") (pinfunction "SHIELD_SH3") (pintype "passive"))
      (node (ref "J4") (pin "SH4") (pinfunction "SHIELD_SH4") (pintype "passive"))
      (node (ref "R1_USB") (pin "1") (pinfunction "1_1") (pintype "bidirectional"))
      (node (ref "R2_EP_DR") (pin "1") (pinfunction "1_1") (pintype "bidirectional"))
      (node (ref "R2_USB") (pin "2") (pinfunction "2_2") (pintype "bidirectional"))
      (node (ref "R3") (pin "1") (pinfunction "1_1") (pintype "bidirectional"))
      (node (ref "R9") (pin "1") (pinfunction "1_1") (pintype "bidirectional"))
      (node (ref "R_TYPE_SEL") (pin "1") (pinfunction "1_1") (pintype "bidirectional"))
      (node (ref "SJ1") (pin "1") (pinfunction "1_1") (pintype "passive"))
      (node (ref "SW_DN") (pin "1") (pinfunction "1_1") (pintype "passive"))
      (node (ref "SW_ENT") (pin "1") (pinfunction "1_1") (pintype "passive"))
      (node (ref "SW_UP") (pin "1") (pinfunction "1_1") (pintype "passive"))
      (node (ref "TP_BAT_GND") (pin "TP") (pinfunction "TP_TP") (pintype "input"))
      (node (ref "TP_GND") (pin "TP") (pinfunction "TP_TP") (pintype "input"))
      (node (ref "U1") (pin "P$74") (pinfunction "VSS_PAD_P$74") (pintype "bidirectional"))
      (node (ref "U1") (pin "P$75") (pinfunction "VSS_PAD_P$75") (pintype "bidirectional"))
      (node (ref "U1") (pin "P$76") (pinfunction "VSS_PAD_P$76") (pintype "bidirectional"))
      (node (ref "U1") (pin "P$77") (pinfunction "VSS_PAD_P$77") (pintype "bidirectional"))
      (node (ref "U1") (pin "P$78") (pinfunction "VSS_PAD_P$78") (pintype "bidirectional"))
      (node (ref "U1") (pin "P$79") (pinfunction "VSS_PAD_P$79") (pintype "bidirectional"))
      (node (ref "U1") (pin "P$80") (pinfunction "VSS_PAD_P$80") (pintype "bidirectional"))
      (node (ref "U1") (pin "P$81") (pinfunction "VSS_PAD_P$81") (pintype "bidirectional"))
      (node (ref "U1") (pin "P$82") (pinfunction "VSS_PAD_P$82") (pintype "bidirectional"))
      (node (ref "U1") (pin "P$83") (pinfunction "VSS_PAD_P$83") (pintype "bidirectional"))
      (node (ref "U1") (pin "P$84") (pinfunction "VSS_PAD_P$84") (pintype "bidirectional"))
      (node (ref "U1") (pin "P$85") (pinfunction "VSS_PAD_P$85") (pintype "bidirectional"))
      (node (ref "U1") (pin "P$86") (pinfunction "VSS_PAD_P$86") (pintype "bidirectional"))
      (node (ref "U1") (pin "P$87") (pinfunction "VSS_PAD_P$87") (pintype "bidirectional"))
      (node (ref "U1") (pin "P$88") (pinfunction "VSS_PAD_P$88") (pintype "bidirectional"))
      (node (ref "U1") (pin "P$89") (pinfunction "VSS_PAD_P$89") (pintype "bidirectional"))
      (node (ref "U1") (pin "P$90") (pinfunction "VSS_PAD_P$90") (pintype "bidirectional"))
      (node (ref "U1") (pin "P$B7") (pinfunction "VSS_P$B7") (pintype "power_in"))
      (node (ref "U1") (pin "P$F23") (pinfunction "VSS_PA_P$F23") (pintype "bidirectional"))
      (node (ref "U3") (pin "1") (pinfunction "CTG_1") (pintype "power_in"))
      (node (ref "U3") (pin "4") (pinfunction "GND_4") (pintype "power_in"))
      (node (ref "U3") (pin "6") (pinfunction "QSTRT_6") (pintype "input"))
      (node (ref "U3") (pin "9") (pinfunction "EP_9") (pintype "power_in"))
      (node (ref "X1") (pin "2") (pinfunction "2_2") (pintype "passive"))
      (node (ref "X1") (pin "4") (pinfunction "4_4") (pintype "passive"))
    )
    (net (code "22") (name "HAPTIC_EN{slash}1.4C") (class "Default")
      (node (ref "IC2") (pin "A1") (pinfunction "EN_A1") (pintype "bidirectional"))
    )
    (net (code "23") (name "HAPTIC_EN{slash}2.6A") (class "Default")
      (node (ref "U1") (pin "P$U1") (pinfunction "P0.12_P$U1") (pintype "bidirectional"))
    )
    (net (code "24") (name "IMU_INT1") (class "Default")
      (node (ref "IC3") (pin "5") (pinfunction "INT1_5") (pintype "bidirectional"))
      (node (ref "U1") (pin "P$N1") (pinfunction "P0.08_P$N1") (pintype "bidirectional"))
    )
    (net (code "25") (name "IMU_INT2") (class "Default")
      (node (ref "IC3") (pin "6") (pinfunction "INT2_6") (pintype "bidirectional"))
      (node (ref "U1") (pin "P$P2") (pinfunction "P1.08_P$P2") (pintype "bidirectional"))
    )
    (net (code "26") (name "LX1") (class "Default")
      (node (ref "IC9") (pin "B2") (pinfunction "SW1_1_B2") (pintype "bidirectional"))
      (node (ref "L7") (pin "1") (pinfunction "1_1") (pintype "bidirectional"))
    )
    (net (code "27") (name "LX2") (class "Default")
      (node (ref "IC9") (pin "D2") (pinfunction "SW2_1_D2") (pintype "bidirectional"))
      (node (ref "IC9") (pin "D3") (pinfunction "SW2_2_D3") (pintype "bidirectional"))
      (node (ref "L7") (pin "2") (pinfunction "2_2") (pintype "bidirectional"))
    )
    (net (code "28") (name "MOSI{slash}1.5B") (class "Default")
      (node (ref "J1") (pin "14") (pinfunction "14_14") (pintype "bidirectional"))
    )
    (net (code "29") (name "MOSI{slash}2.2D") (class "Default")
      (node (ref "U1") (pin "P$B13") (pinfunction "P0.03/AIN1_P$B13") (pintype "bidirectional"))
    )
    (net (code "30") (name "N$3") (class "Default")
      (node (ref "C6") (pin "1") (pinfunction "1_1") (pintype "passive"))
      (node (ref "U1") (pin "P$W1") (pinfunction "VDD_P$W1") (pintype "power_in"))
      (node (ref "U1") (pin "P$Y2") (pinfunction "VDDH_P$Y2") (pintype "power_in"))
    )
    (net (code "31") (name "Net-(ANT1-FEED)") (class "Default")
      (node (ref "ANT1") (pin "1") (pinfunction "FEED_1") (pintype "input"))
      (node (ref "C22") (pin "1") (pinfunction "1_1") (pintype "passive"))
      (node (ref "C4") (pin "1") (pinfunction "1_1") (pintype "passive"))
      (node (ref "L1") (pin "2") (pinfunction "2_2") (pintype "passive"))
    )
    (net (code "32") (name "Net-(D2-K)") (class "Default")
      (node (ref "C2-EP-DR") (pin "1") (pinfunction "1_1") (pintype "passive"))
      (node (ref "D2") (pin "1") (pinfunction "K_1") (pintype "bidirectional"))
      (node (ref "D4") (pin "2") (pinfunction "A_2") (pintype "bidirectional"))
    )
    (net (code "33") (name "Net-(D5-A)") (class "Default")
      (node (ref "C2-EP-DR") (pin "2") (pinfunction "2_2") (pintype "passive"))
      (node (ref "D5") (pin "2") (pinfunction "A_2") (pintype "bidirectional"))
      (node (ref "L5") (pin "2") (pinfunction "2_2") (pintype "passive"))
      (node (ref "Q3") (pin "3") (pinfunction "D_3") (pintype "bidirectional"))
    )
    (net (code "34") (name "Net-(EPD_C1-Pad2)") (class "Default")
      (node (ref "EPD_C1") (pin "2") (pinfunction "2_2") (pintype "passive"))
      (node (ref "J1") (pin "5") (pinfunction "5_5") (pintype "bidirectional"))
    )
    (net (code "35") (name "Net-(EPD_C2-Pad2)") (class "Default")
      (node (ref "EPD_C2") (pin "2") (pinfunction "2_2") (pintype "passive"))
      (node (ref "J1") (pin "4") (pinfunction "4_4") (pintype "bidirectional"))
    )
    (net (code "36") (name "Net-(EPD_C6-Pad2)") (class "Default")
      (node (ref "EPD_C6") (pin "2") (pinfunction "2_2") (pintype "passive"))
      (node (ref "J1") (pin "18") (pinfunction "18_18") (pintype "bidirectional"))
    )
    (net (code "37") (name "Net-(EPD_C7-Pad2)") (class "Default")
      (node (ref "EPD_C7") (pin "2") (pinfunction "2_2") (pintype "passive"))
      (node (ref "J1") (pin "19") (pinfunction "19_19") (pintype "bidirectional"))
    )
    (net (code "38") (name "Net-(EPD_C8-Pad2)") (class "Default")
      (node (ref "EPD_C8") (pin "2") (pinfunction "2_2") (pintype "passive"))
      (node (ref "J1") (pin "20") (pinfunction "20_20") (pintype "bidirectional"))
    )
    (net (code "39") (name "Net-(EPD_C10-Pad2)") (class "Default")
      (node (ref "EPD_C10") (pin "2") (pinfunction "2_2") (pintype "passive"))
      (node (ref "J1") (pin "22") (pinfunction "22_22") (pintype "bidirectional"))
    )
    (net (code "40") (name "Net-(EPD_C12-Pad2)") (class "Default")
      (node (ref "EPD_C12") (pin "2") (pinfunction "2_2") (pintype "passive"))
      (node (ref "J1") (pin "24") (pinfunction "24_24") (pintype "bidirectional"))
    )
    (net (code "41") (name "Net-(IC1-TS{slash}MR)") (class "Default")
      (node (ref "IC1") (pin "D1") (pinfunction "TS/MR_D1") (pintype "bidirectional"))
      (node (ref "R9") (pin "2") (pinfunction "2_2") (pintype "bidirectional"))
    )
    (net (code "42") (name "Net-(IC2-REG)") (class "Default")
      (node (ref "C32") (pin "1") (pinfunction "1_1") (pintype "passive"))
      (node (ref "IC2") (pin "A2") (pinfunction "REG_A2") (pintype "bidirectional"))
    )
    (net (code "43") (name "Net-(IC3-SDO)") (class "Default")
      (node (ref "IC3") (pin "1") (pinfunction "SDO_1") (pintype "bidirectional"))
      (node (ref "R3") (pin "2") (pinfunction "2_2") (pintype "bidirectional"))
    )
    (net (code "44") (name "Net-(IC9-SCL)") (class "Default")
      (node (ref "IC9") (pin "D1") (pinfunction "SCL_D1") (pintype "bidirectional"))
      (node (ref "R4") (pin "2") (pinfunction "2_2") (pintype "bidirectional"))
    )
    (net (code "45") (name "Net-(IC9-SDA)") (class "Default")
      (node (ref "IC9") (pin "E1") (pinfunction "SDA_E1") (pintype "bidirectional"))
      (node (ref "R2") (pin "2") (pinfunction "2_2") (pintype "bidirectional"))
    )
    (net (code "46") (name "Net-(J4-CC1)") (class "Default")
      (node (ref "J4") (pin "A5") (pinfunction "CC1_A5") (pintype "bidirectional"))
      (node (ref "R1_USB") (pin "2") (pinfunction "2_2") (pintype "bidirectional"))
    )
    (net (code "47") (name "Net-(J4-CC2)") (class "Default")
      (node (ref "J4") (pin "B5") (pinfunction "CC2_B5") (pintype "bidirectional"))
      (node (ref "R2_USB") (pin "1") (pinfunction "1_1") (pintype "bidirectional"))
    )
    (net (code "48") (name "Net-(L2-Pad2)") (class "Default")
      (node (ref "L2") (pin "2") (pinfunction "2_2") (pintype "passive"))
      (node (ref "L3") (pin "1") (pinfunction "1_1") (pintype "passive"))
    )
    (net (code "49") (name "Net-(R1_EP_DR-Pad1)") (class "Default")
      (node (ref "R1_EP_DR") (pin "1") (pinfunction "1_1") (pintype "bidirectional"))
      (node (ref "R_TYPE_SEL") (pin "2") (pinfunction "2_2") (pintype "bidirectional"))
      (node (ref "SJ1") (pin "2") (pinfunction "2_2") (pintype "passive"))
    )
    (net (code "50") (name "Net-(U1-ANT)") (class "Default")
      (node (ref "C3") (pin "1") (pinfunction "1_1") (pintype "passive"))
      (node (ref "L1") (pin "1") (pinfunction "1_1") (pintype "passive"))
      (node (ref "U1") (pin "P$H23") (pinfunction "ANT_P$H23") (pintype "bidirectional"))
    )
    (net (code "51") (name "Net-(U1-DCC)") (class "Default")
      (node (ref "L2") (pin "1") (pinfunction "1_1") (pintype "passive"))
      (node (ref "U1") (pin "P$B3") (pinfunction "DCC_P$B3") (pintype "output"))
    )
    (net (code "52") (name "Net-(U1-DEC1)") (class "Default")
      (node (ref "C5") (pin "2") (pinfunction "2_2") (pintype "passive"))
      (node (ref "U1") (pin "P$C1") (pinfunction "DEC1_P$C1") (pintype "power_in"))
    )
    (net (code "53") (name "Net-(U1-DEC2)") (class "Default")
      (node (ref "C13") (pin "1") (pinfunction "1_1") (pintype "passive"))
      (node (ref "U1") (pin "P$A18") (pinfunction "DEC2_P$A18") (pintype "bidirectional"))
    )
    (net (code "54") (name "Net-(U1-DEC3)") (class "Default")
      (node (ref "C11") (pin "1") (pinfunction "1_1") (pintype "passive"))
      (node (ref "U1") (pin "P$D23") (pinfunction "DEC3_P$D23") (pintype "bidirectional"))
    )
    (net (code "55") (name "Net-(U1-DEC3V3)") (class "Default")
      (node (ref "C20") (pin "1") (pinfunction "1_1") (pintype "passive"))
      (node (ref "U1") (pin "P$AC5") (pinfunction "DEC3V3_P$AC5") (pintype "bidirectional"))
    )
    (net (code "56") (name "Net-(U1-DEC4)") (class "Default")
      (node (ref "C10") (pin "1") (pinfunction "1_1") (pintype "passive"))
      (node (ref "C15") (pin "1") (pinfunction "1_1") (pintype "passive"))
      (node (ref "C16") (pin "1") (pinfunction "1_1") (pintype "passive"))
      (node (ref "L3") (pin "2") (pinfunction "2_2") (pintype "passive"))
      (node (ref "U1") (pin "P$B5") (pinfunction "DEC4_P$B5") (pintype "power_in"))
      (node (ref "U1") (pin "P$E24") (pinfunction "DEC6_P$E24") (pintype "bidirectional"))
    )
    (net (code "57") (name "Net-(U1-DEC5)") (class "Default")
      (node (ref "C9") (pin "1") (pinfunction "1_1") (pintype "passive"))
      (node (ref "U1") (pin "P$N24") (pinfunction "DEC5_P$N24") (pintype "bidirectional"))
    )
    (net (code "58") (name "Net-(U1-P0.00{slash}XL1)") (class "Default")
      (node (ref "C17") (pin "2") (pinfunction "2_2") (pintype "passive"))
      (node (ref "U1") (pin "P$D2") (pinfunction "P0.00/XL1_P$D2") (pintype "bidirectional"))
      (node (ref "X2") (pin "1") (pinfunction "1_1") (pintype "passive"))
    )
    (net (code "59") (name "Net-(U1-P0.01{slash}XL2)") (class "Default")
      (node (ref "C18") (pin "2") (pinfunction "2_2") (pintype "passive"))
      (node (ref "U1") (pin "P$F2") (pinfunction "P0.01/XL2_P$F2") (pintype "bidirectional"))
      (node (ref "X2") (pin "2") (pinfunction "2_2") (pintype "passive"))
    )
    (net (code "60") (name "Net-(U1-XC1)") (class "Default")
      (node (ref "C1") (pin "1") (pinfunction "1_1") (pintype "passive"))
      (node (ref "U1") (pin "P$B24") (pinfunction "XC1_P$B24") (pintype "input"))
      (node (ref "X1") (pin "1") (pinfunction "1_1") (pintype "passive"))
    )
    (net (code "61") (name "Net-(U1-XC2)") (class "Default")
      (node (ref "C2") (pin "1") (pinfunction "1_1") (pintype "passive"))
      (node (ref "U1") (pin "P$A23") (pinfunction "XC2_P$A23") (pintype "output"))
      (node (ref "X1") (pin "3") (pinfunction "3_3") (pintype "passive"))
    )
    (net (code "62") (name "OUT+") (class "Default")
      (node (ref "IC2") (pin "A3") (pinfunction "OUT+_A3") (pintype "bidirectional"))
      (node (ref "TP_OP") (pin "TP") (pinfunction "TP_TP") (pintype "input"))
    )
    (net (code "63") (name "OUT-") (class "Default")
      (node (ref "IC2") (pin "C3") (pinfunction "OUT-_C3") (pintype "bidirectional"))
      (node (ref "TP_ON") (pin "TP") (pinfunction "TP_TP") (pintype "input"))
    )
    (net (code "64") (name "P0.04") (class "Default")
      (node (ref "U1") (pin "P$J1") (pinfunction "P0.04/AIN2_P$J1") (pintype "bidirectional"))
    )
    (net (code "65") (name "P0.09") (class "Default")
      (node (ref "U1") (pin "P$L24") (pinfunction "P0.09/NFC1_P$L24") (pintype "bidirectional"))
    )
    (net (code "66") (name "P0.13{slash}1.5D") (class "Default")
      (node (ref "C30") (pin "1") (pinfunction "1_1") (pintype "passive"))
      (node (ref "R5") (pin "1") (pinfunction "1_1") (pintype "bidirectional"))
      (node (ref "SW_UP") (pin "2") (pinfunction "2_2") (pintype "passive"))
    )
    (net (code "67") (name "P0.13{slash}2.6C") (class "Default")
      (node (ref "U1") (pin "P$AD8") (pinfunction "P0.13_P$AD8") (pintype "bidirectional"))
    )
    (net (code "68") (name "P0.14{slash}1.5D") (class "Default")
      (node (ref "C31") (pin "1") (pinfunction "1_1") (pintype "passive"))
      (node (ref "R8") (pin "1") (pinfunction "1_1") (pintype "bidirectional"))
      (node (ref "SW_ENT") (pin "2") (pinfunction "2_2") (pintype "passive"))
    )
    (net (code "69") (name "P0.14{slash}2.7C") (class "Default")
      (node (ref "U1") (pin "P$AC9") (pinfunction "P0.14_P$AC9") (pintype "bidirectional"))
    )
    (net (code "70") (name "P0.19") (class "Default")
      (node (ref "U1") (pin "P$AC15") (pinfunction "P0.19_P$AC15") (pintype "bidirectional"))
    )
    (net (code "71") (name "P0.20") (class "Default")
      (node (ref "U1") (pin "P$AD16") (pinfunction "P0.20_P$AD16") (pintype "bidirectional"))
    )
    (net (code "72") (name "P0.21") (class "Default")
      (node (ref "U1") (pin "P$AC17") (pinfunction "P0.21_P$AC17") (pintype "bidirectional"))
    )
    (net (code "73") (name "P0.22") (class "Default")
      (node (ref "U1") (pin "P$AD18") (pinfunction "P0.22_P$AD18") (pintype "bidirectional"))
    )
    (net (code "74") (name "P0.23") (class "Default")
      (node (ref "U1") (pin "P$AC19") (pinfunction "P0.23_P$AC19") (pintype "bidirectional"))
    )
    (net (code "75") (name "P0.24") (class "Default")
      (node (ref "U1") (pin "P$AD20") (pinfunction "P0.24_P$AD20") (pintype "bidirectional"))
    )
    (net (code "76") (name "P0.25") (class "Default")
      (node (ref "U1") (pin "P$AC21") (pinfunction "P0.25_P$AC21") (pintype "bidirectional"))
    )
    (net (code "77") (name "P0.26") (class "Default")
      (node (ref "U1") (pin "P$G1") (pinfunction "P0.26_P$G1") (pintype "bidirectional"))
    )
    (net (code "78") (name "P0.27") (class "Default")
      (node (ref "U1") (pin "P$H2") (pinfunction "P0.27_P$H2") (pintype "bidirectional"))
    )
    (net (code "79") (name "P0.28") (class "Default")
      (node (ref "U1") (pin "P$B11") (pinfunction "P0.28/AIN4_P$B11") (pintype "bidirectional"))
    )
    (net (code "80") (name "P0.29") (class "Default")
      (node (ref "U1") (pin "P$A10") (pinfunction "P0.29/AIN5_P$A10") (pintype "bidirectional"))
    )
    (net (code "81") (name "P0.30") (class "Default")
      (node (ref "U1") (pin "P$B9") (pinfunction "P0.30/AIN6_P$B9") (pintype "bidirectional"))
    )
    (net (code "82") (name "P0.31") (class "Default")
      (node (ref "U1") (pin "P$A8") (pinfunction "P0.31/AIN7_P$A8") (pintype "bidirectional"))
    )
    (net (code "83") (name "P1.01{slash}1.6C") (class "Default")
      (node (ref "Q1") (pin "1") (pinfunction "G_1") (pintype "bidirectional"))
      (node (ref "R_PWR_EPD") (pin "1") (pinfunction "1_1") (pintype "bidirectional"))
    )
    (net (code "84") (name "P1.01{slash}2.4B") (class "Default")
      (node (ref "U1") (pin "P$Y23") (pinfunction "P1.01_P$Y23") (pintype "bidirectional"))
    )
    (net (code "85") (name "P1.02{slash}1.6C") (class "Default")
      (node (ref "C29") (pin "1") (pinfunction "1_1") (pintype "passive"))
      (node (ref "R7") (pin "1") (pinfunction "1_1") (pintype "bidirectional"))
      (node (ref "SW_DN") (pin "2") (pinfunction "2_2") (pintype "passive"))
    )
    (net (code "86") (name "P1.02{slash}2.8C") (class "Default")
      (node (ref "U1") (pin "P$W24") (pinfunction "P1.02_P$W24") (pintype "bidirectional"))
    )
    (net (code "87") (name "P1.03") (class "Default")
      (node (ref "U1") (pin "P$V23") (pinfunction "P1.03_P$V23") (pintype "bidirectional"))
    )
    (net (code "88") (name "P1.04") (class "Default")
      (node (ref "U1") (pin "P$U24") (pinfunction "P1.04_P$U24") (pintype "bidirectional"))
    )
    (net (code "89") (name "P1.05") (class "Default")
      (node (ref "U1") (pin "P$T23") (pinfunction "P1.05_P$T23") (pintype "bidirectional"))
    )
    (net (code "90") (name "P1.07") (class "Default")
      (node (ref "U1") (pin "P$P23") (pinfunction "P1.07_P$P23") (pintype "bidirectional"))
    )
    (net (code "91") (name "P1.09") (class "Default")
      (node (ref "U1") (pin "P$R1") (pinfunction "P1.09_P$R1") (pintype "bidirectional"))
    )
    (net (code "92") (name "P1.10") (class "Default")
      (node (ref "U1") (pin "P$A20") (pinfunction "P1.10_P$A20") (pintype "bidirectional"))
    )
    (net (code "93") (name "P1.11") (class "Default")
      (node (ref "U1") (pin "P$B19") (pinfunction "P1.11_P$B19") (pintype "bidirectional"))
    )
    (net (code "94") (name "P1.12") (class "Default")
      (node (ref "U1") (pin "P$B17") (pinfunction "P1.12_P$B17") (pintype "bidirectional"))
    )
    (net (code "95") (name "P1.13") (class "Default")
      (node (ref "U1") (pin "P$A16") (pinfunction "P1.13_P$A16") (pintype "bidirectional"))
    )
    (net (code "96") (name "P1.14") (class "Default")
      (node (ref "U1") (pin "P$B15") (pinfunction "P1.14_P$B15") (pintype "bidirectional"))
    )
    (net (code "97") (name "P1.15") (class "Default")
      (node (ref "U1") (pin "P$A14") (pinfunction "P1.15_P$A14") (pintype "bidirectional"))
    )
    (net (code "98") (name "P1{slash}06") (class "Default")
      (node (ref "U1") (pin "P$R24") (pinfunction "P1.06_P$R24") (pintype "bidirectional"))
    )
    (net (code "99") (name "PMIC_INT") (class "Default")
      (node (ref "IC1") (pin "A1") (pinfunction "~{INT}_A1") (pintype "bidirectional"))
      (node (ref "U1") (pin "P$T2") (pinfunction "P0.11_P$T2") (pintype "bidirectional"))
    )
    (net (code "100") (name "PREVGH") (class "Default")
      (node (ref "D5") (pin "1") (pinfunction "K_1") (pintype "bidirectional"))
      (node (ref "EPD_C11") (pin "2") (pinfunction "2_2") (pintype "passive"))
      (node (ref "J1") (pin "23") (pinfunction "23_23") (pintype "bidirectional"))
    )
    (net (code "101") (name "PREVGL") (class "Default")
      (node (ref "D2") (pin "2") (pinfunction "A_2") (pintype "bidirectional"))
      (node (ref "EPD_C9") (pin "2") (pinfunction "2_2") (pintype "passive"))
      (node (ref "J1") (pin "21") (pinfunction "21_21") (pintype "bidirectional"))
    )
    (net (code "102") (name "RESE") (class "Default")
      (node (ref "J1") (pin "3") (pinfunction "3_3") (pintype "bidirectional"))
      (node (ref "Q3") (pin "2") (pinfunction "S_2") (pintype "bidirectional"))
      (node (ref "R1_EP_DR") (pin "2") (pinfunction "2_2") (pintype "bidirectional"))
    )
    (net (code "103") (name "RESET") (class "Default")
      (node (ref "J2") (pin "6") (pinfunction "6_6") (pintype "bidirectional"))
      (node (ref "TP_RESET") (pin "TP") (pinfunction "TP_TP") (pintype "input"))
      (node (ref "U1") (pin "P$AC13") (pinfunction "P0.18/RESET_P$AC13") (pintype "bidirectional"))
    )
    (net (code "104") (name "SCK{slash}1.5B") (class "Default")
      (node (ref "J1") (pin "13") (pinfunction "13_13") (pintype "bidirectional"))
    )
    (net (code "105") (name "SCK{slash}2.2D") (class "Default")
      (node (ref "U1") (pin "P$A12") (pinfunction "P0.02/AIN0_P$A12") (pintype "bidirectional"))
    )
    (net (code "106") (name "SCL{slash}1.4C") (class "Default")
      (node (ref "IC2") (pin "C1") (pinfunction "SCL_C1") (pintype "bidirectional"))
      (node (ref "U3") (pin "7") (pinfunction "SCL_7") (pintype "input"))
    )
    (net (code "107") (name "SCL{slash}2.4C") (class "Default")
      (node (ref "IC1") (pin "B1") (pinfunction "SCL_B1") (pintype "bidirectional"))
      (node (ref "IC3") (pin "12") (pinfunction "SCX_12") (pintype "bidirectional"))
      (node (ref "R17") (pin "2") (pinfunction "2_2") (pintype "bidirectional"))
      (node (ref "R4") (pin "1") (pinfunction "1_1") (pintype "bidirectional"))
      (node (ref "TP_SCL") (pin "TP") (pinfunction "TP_TP") (pintype "input"))
      (node (ref "U1") (pin "P$M2") (pinfunction "P0.07_P$M2") (pintype "bidirectional"))
    )
    (net (code "108") (name "SDA{slash}1.4C") (class "Default")
      (node (ref "IC2") (pin "B2") (pinfunction "SDA_B2") (pintype "bidirectional"))
      (node (ref "U3") (pin "8") (pinfunction "SDA_8") (pintype "bidirectional"))
    )
    (net (code "109") (name "SDA{slash}2.4C") (class "Default")
      (node (ref "IC1") (pin "C1") (pinfunction "SDA_C1") (pintype "bidirectional"))
      (node (ref "IC3") (pin "2") (pinfunction "SDX_2") (pintype "bidirectional"))
      (node (ref "R18") (pin "2") (pinfunction "2_2") (pintype "bidirectional"))
      (node (ref "R2") (pin "1") (pinfunction "1_1") (pintype "bidirectional"))
      (node (ref "TP_SDA") (pin "TP") (pinfunction "TP_TP") (pintype "input"))
      (node (ref "U1") (pin "P$L1") (pinfunction "P0.06_P$L1") (pintype "bidirectional"))
    )
    (net (code "110") (name "SWDCLK") (class "Default")
      (node (ref "J2") (pin "4") (pinfunction "4_4") (pintype "bidirectional"))
      (node (ref "TP_SWDCLK") (pin "TP") (pinfunction "TP_TP") (pintype "input"))
      (node (ref "U1") (pin "P$AA24") (pinfunction "SWDCLK_P$AA24") (pintype "input"))
    )
    (net (code "111") (name "SWDIO") (class "Default")
      (node (ref "J2") (pin "2") (pinfunction "2_2") (pintype "bidirectional"))
      (node (ref "TP_SWDIO") (pin "TP") (pinfunction "TP_TP") (pintype "input"))
      (node (ref "U1") (pin "P$AC24") (pinfunction "SWDIO_P$AC24") (pintype "bidirectional"))
    )
    (net (code "112") (name "SWO") (class "Default")
      (node (ref "TP_SWO") (pin "TP") (pinfunction "TP_TP") (pintype "input"))
      (node (ref "U1") (pin "P$AD22") (pinfunction "P1.00_P$AD22") (pintype "bidirectional"))
    )
    (net (code "113") (name "VBAT{slash}1.2A") (class "Default")
      (node (ref "C27") (pin "2") (pinfunction "2_2") (pintype "passive"))
      (node (ref "TP_VBAT") (pin "TP") (pinfunction "TP_TP") (pintype "input"))
      (node (ref "U3") (pin "2") (pinfunction "CELL_2") (pintype "power_in"))
      (node (ref "U3") (pin "3") (pinfunction "VDD_3") (pintype "power_in"))
    )
    (net (code "114") (name "VBAT{slash}2.5C") (class "Default")
      (node (ref "C37") (pin "1") (pinfunction "1_1") (pintype "passive"))
      (node (ref "IC1") (pin "C2") (pinfunction "BAT_C2") (pintype "bidirectional"))
    )
    (net (code "115") (name "VBUS{slash}1.5D") (class "Default")
      (node (ref "C42") (pin "1") (pinfunction "1_1") (pintype "passive"))
      (node (ref "C43") (pin "1") (pinfunction "1_1") (pintype "passive"))
      (node (ref "D3") (pin "5") (pinfunction "VBUS_5") (pintype "bidirectional"))
      (node (ref "J4") (pin "A4_B9") (pinfunction "VBUS_A4_B9") (pintype "power_in"))
      (node (ref "J4") (pin "A9_B4") (pinfunction "VBUS_A9_B4") (pintype "power_in"))
    )
    (net (code "116") (name "VBUS{slash}2.6D") (class "Default")
      (node (ref "C21") (pin "1") (pinfunction "1_1") (pintype "passive"))
      (node (ref "C38") (pin "1") (pinfunction "1_1") (pintype "passive"))
      (node (ref "IC1") (pin "A2") (pinfunction "IN_A2") (pintype "bidirectional"))
      (node (ref "U1") (pin "P$AD2") (pinfunction "VBUS_P$AD2") (pintype "power_in"))
    )
    (net (code "117") (name "VREG") (class "Default")
      (node (ref "C23") (pin "2") (pinfunction "2_2") (pintype "passive"))
      (node (ref "C24") (pin "1") (pinfunction "1_1") (pintype "passive"))
      (node (ref "C39") (pin "1") (pinfunction "1_1") (pintype "passive"))
      (node (ref "IC1") (pin "B2") (pinfunction "SYS_B2") (pintype "bidirectional"))
      (node (ref "IC9") (pin "A1") (pinfunction "EN_A1") (pintype "bidirectional"))
      (node (ref "IC9") (pin "A2") (pinfunction "VIN_1_A2") (pintype "bidirectional"))
      (node (ref "IC9") (pin "A3") (pinfunction "VIN_2_A3") (pintype "bidirectional"))
    )
    (net (code "118") (name "unconnected-(ANT1-NC-Pad2)") (class "Default")
      (node (ref "ANT1") (pin "2") (pinfunction "NC_2") (pintype "no_connect"))
    )
    (net (code "119") (name "unconnected-(IC3-ASCL-Pad11)") (class "Default")
      (node (ref "IC3") (pin "11") (pinfunction "ASCL_11") (pintype "bidirectional"))
    )
    (net (code "120") (name "unconnected-(IC3-ASDA-Pad4)") (class "Default")
      (node (ref "IC3") (pin "4") (pinfunction "ASDA_4") (pintype "bidirectional"))
    )
    (net (code "121") (name "unconnected-(IC9-AGND-PadC1)") (class "Default")
      (node (ref "IC9") (pin "C1") (pinfunction "AGND_C1") (pintype "bidirectional"))
    )
    (net (code "122") (name "unconnected-(IC9-SW1_2-PadB3)") (class "Default")
      (node (ref "IC9") (pin "B3") (pinfunction "SW1_2_B3") (pintype "bidirectional"))
    )
    (net (code "123") (name "unconnected-(J1-Pad1)") (class "Default")
      (node (ref "J1") (pin "1") (pinfunction "1_1") (pintype "bidirectional"))
    )
    (net (code "124") (name "unconnected-(J1-Pad6)") (class "Default")
      (node (ref "J1") (pin "6") (pinfunction "6_6") (pintype "bidirectional"))
    )
    (net (code "125") (name "unconnected-(J1-Pad7)") (class "Default")
      (node (ref "J1") (pin "7") (pinfunction "7_7") (pintype "bidirectional"))
    )
    (net (code "126") (name "unconnected-(J4-SBU1-PadA8)") (class "Default")
      (node (ref "J4") (pin "A8") (pinfunction "SBU1_A8") (pintype "bidirectional"))
    )
    (net (code "127") (name "unconnected-(J4-SBU2-PadB8)") (class "Default")
      (node (ref "J4") (pin "B8") (pinfunction "SBU2_B8") (pintype "bidirectional"))
    )
    (net (code "128") (name "unconnected-(U1-DCCH-PadP$AB2)") (class "Default")
      (node (ref "U1") (pin "P$AB2") (pinfunction "DCCH_P$AB2") (pintype "bidirectional"))
    )
  )
)
